# Passive_Mult.net
KiCad netlist of a schematic drawn in EAGLE
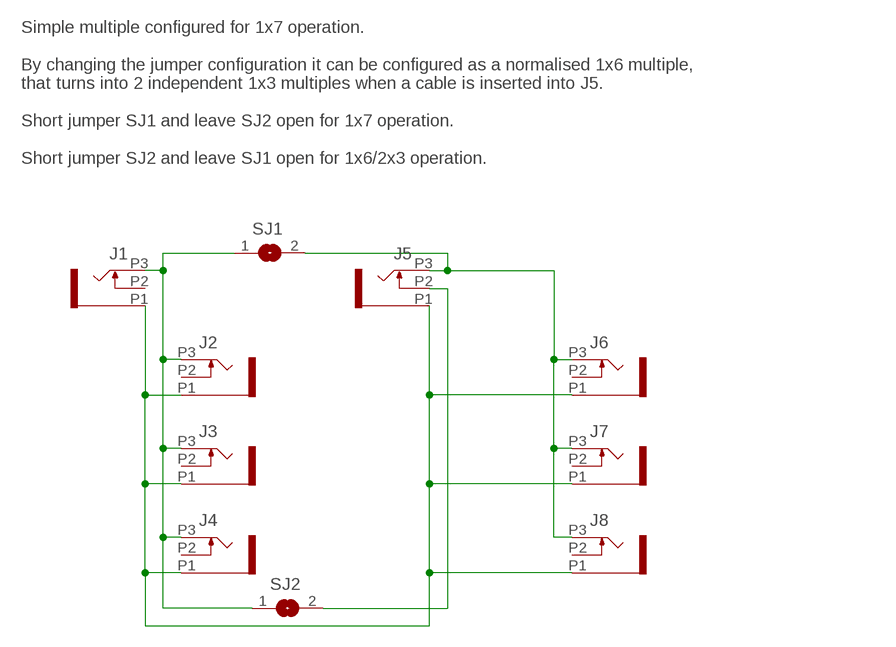
[diagram p0: schematic, sheet 1]

(export (version "E")
  (design (tool "Eeschema 10.0.6"))
  (components
    (comp (ref "J1")
      (value "OG-PJ301_PJ301_THONKICONN4")
      (footprint "eagle-import:OG-PJ301_WQP_PJ_301M4")
      (libsource (lib "eagle-import") (part "OG-PJ301_PJ301_THONKICONN4"))
    )
    (comp (ref "J2")
      (value "OG-PJ301_PJ301_THONKICONN4")
      (footprint "eagle-import:OG-PJ301_WQP_PJ_301M4")
      (libsource (lib "eagle-import") (part "OG-PJ301_PJ301_THONKICONN4"))
    )
    (comp (ref "J3")
      (value "OG-PJ301_PJ301_THONKICONN4")
      (footprint "eagle-import:OG-PJ301_WQP_PJ_301M4")
      (libsource (lib "eagle-import") (part "OG-PJ301_PJ301_THONKICONN4"))
    )
    (comp (ref "J4")
      (value "OG-PJ301_PJ301_THONKICONN4")
      (footprint "eagle-import:OG-PJ301_WQP_PJ_301M4")
      (libsource (lib "eagle-import") (part "OG-PJ301_PJ301_THONKICONN4"))
    )
    (comp (ref "J5")
      (value "OG-PJ301_PJ301_THONKICONN4")
      (footprint "eagle-import:OG-PJ301_WQP_PJ_301M4")
      (libsource (lib "eagle-import") (part "OG-PJ301_PJ301_THONKICONN4"))
    )
    (comp (ref "J6")
      (value "OG-PJ301_PJ301_THONKICONN4")
      (footprint "eagle-import:OG-PJ301_WQP_PJ_301M4")
      (libsource (lib "eagle-import") (part "OG-PJ301_PJ301_THONKICONN4"))
    )
    (comp (ref "J7")
      (value "OG-PJ301_PJ301_THONKICONN4")
      (footprint "eagle-import:OG-PJ301_WQP_PJ_301M4")
      (libsource (lib "eagle-import") (part "OG-PJ301_PJ301_THONKICONN4"))
    )
    (comp (ref "J8")
      (value "OG-PJ301_PJ301_THONKICONN4")
      (footprint "eagle-import:OG-PJ301_WQP_PJ_301M4")
      (libsource (lib "eagle-import") (part "OG-PJ301_PJ301_THONKICONN4"))
    )
    (comp (ref "SJ1") (value "SJ") (footprint "eagle-import:SJ") (libsource (lib "eagle-import") (part "SJ")))
    (comp (ref "SJ2") (value "SJ") (footprint "eagle-import:SJ") (libsource (lib "eagle-import") (part "SJ")))
  )
  (nets
    (net (code "1") (name "Net-(J1-1)") (class "Default")
      (node (ref "J1") (pin "P1") (pinfunction "1_P1") (pintype "passive"))
      (node (ref "J2") (pin "P1") (pinfunction "1_P1") (pintype "passive"))
      (node (ref "J3") (pin "P1") (pinfunction "1_P1") (pintype "passive"))
      (node (ref "J4") (pin "P1") (pinfunction "1_P1") (pintype "passive"))
      (node (ref "J5") (pin "P1") (pinfunction "1_P1") (pintype "passive"))
      (node (ref "J6") (pin "P1") (pinfunction "1_P1") (pintype "passive"))
      (node (ref "J7") (pin "P1") (pinfunction "1_P1") (pintype "passive"))
      (node (ref "J8") (pin "P1") (pinfunction "1_P1") (pintype "passive"))
    )
    (net (code "2") (name "Net-(J1-3)") (class "Default")
      (node (ref "J1") (pin "P3") (pinfunction "3_P3") (pintype "passive"))
      (node (ref "J2") (pin "P3") (pinfunction "3_P3") (pintype "passive"))
      (node (ref "J3") (pin "P3") (pinfunction "3_P3") (pintype "passive"))
      (node (ref "J4") (pin "P3") (pinfunction "3_P3") (pintype "passive"))
      (node (ref "SJ1") (pin "1") (pinfunction "1_1") (pintype "passive"))
      (node (ref "SJ2") (pin "1") (pinfunction "1_1") (pintype "passive"))
    )
    (net (code "3") (name "Net-(J5-2)") (class "Default")
      (node (ref "J5") (pin "P2") (pinfunction "2_P2") (pintype "passive"))
      (node (ref "SJ2") (pin "2") (pinfunction "2_2") (pintype "passive"))
    )
    (net (code "4") (name "Net-(J5-3)") (class "Default")
      (node (ref "J5") (pin "P3") (pinfunction "3_P3") (pintype "passive"))
      (node (ref "J6") (pin "P3") (pinfunction "3_P3") (pintype "passive"))
      (node (ref "J7") (pin "P3") (pinfunction "3_P3") (pintype "passive"))
      (node (ref "J8") (pin "P3") (pinfunction "3_P3") (pintype "passive"))
      (node (ref "SJ1") (pin "2") (pinfunction "2_2") (pintype "passive"))
    )
    (net (code "5") (name "unconnected-(J1-2-PadP2)") (class "Default")
      (node (ref "J1") (pin "P2") (pinfunction "2_P2") (pintype "passive"))
    )
    (net (code "6") (name "unconnected-(J2-2-PadP2)") (class "Default")
      (node (ref "J2") (pin "P2") (pinfunction "2_P2") (pintype "passive"))
    )
    (net (code "7") (name "unconnected-(J3-2-PadP2)") (class "Default")
      (node (ref "J3") (pin "P2") (pinfunction "2_P2") (pintype "passive"))
    )
    (net (code "8") (name "unconnected-(J4-2-PadP2)") (class "Default")
      (node (ref "J4") (pin "P2") (pinfunction "2_P2") (pintype "passive"))
    )
    (net (code "9") (name "unconnected-(J6-2-PadP2)") (class "Default")
      (node (ref "J6") (pin "P2") (pinfunction "2_P2") (pintype "passive"))
    )
    (net (code "10") (name "unconnected-(J7-2-PadP2)") (class "Default")
      (node (ref "J7") (pin "P2") (pinfunction "2_P2") (pintype "passive"))
    )
    (net (code "11") (name "unconnected-(J8-2-PadP2)") (class "Default")
      (node (ref "J8") (pin "P2") (pinfunction "2_P2") (pintype "passive"))
    )
  )
)
